# LumiBeePCB_v1A_2130spi_1.net
KiCad netlist of a schematic drawn in EAGLE
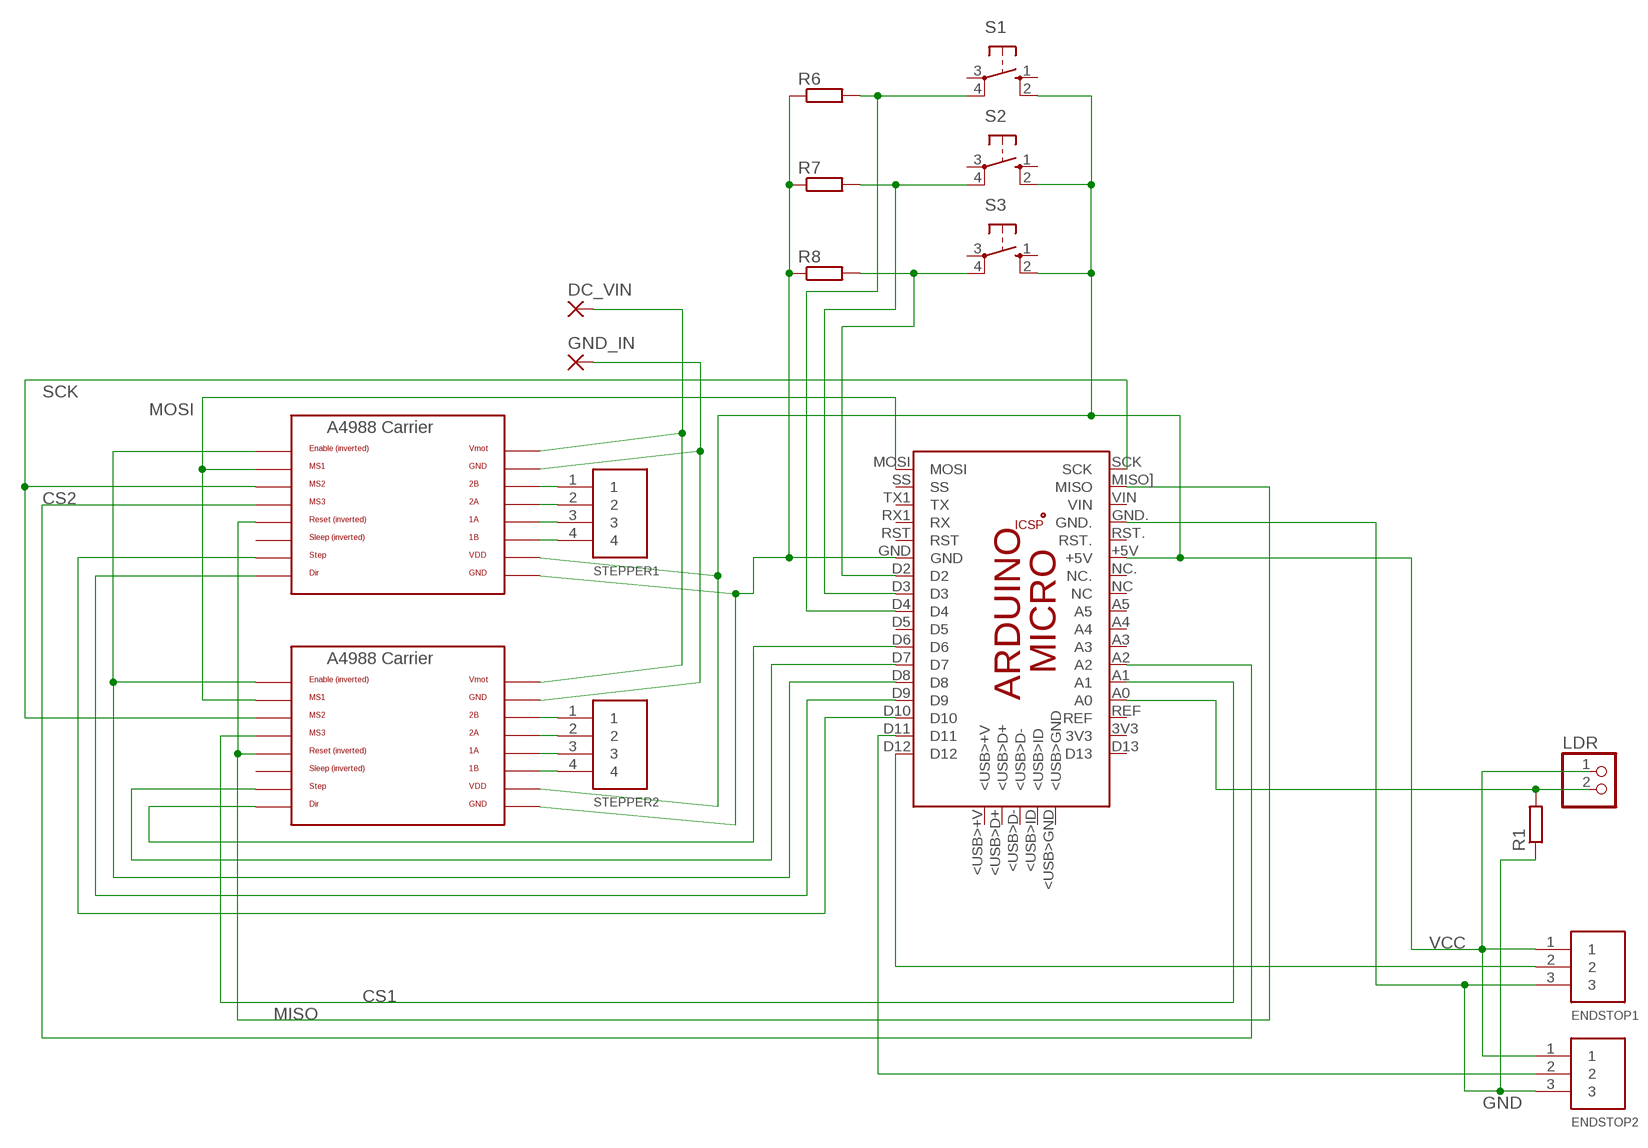
[diagram p0: schematic, sheet 1]

(export (version "E")
  (design (tool "Eeschema 10.0.6"))
  (components
    (comp (ref "DC_VIN")
      (value "2,54/0,8")
      (footprint "eagle-import:2,54_0,8")
      (libsource (lib "eagle-import") (part "2,54/0,8"))
    )
    (comp (ref "ENDSTOP1")
      (value "3PIN")
      (footprint "eagle-import:B3B-PH-K-S")
      (libsource (lib "eagle-import") (part "3PIN"))
    )
    (comp (ref "ENDSTOP2")
      (value "3PIN")
      (footprint "eagle-import:B3B-PH-K-S")
      (libsource (lib "eagle-import") (part "3PIN"))
    )
    (comp (ref "GND_IN")
      (value "2,54/0,8")
      (footprint "eagle-import:2,54_0,8")
      (libsource (lib "eagle-import") (part "2,54/0,8"))
    )
    (comp (ref "LDR")
      (value "PINHD-1X2")
      (footprint "eagle-import:1X02")
      (libsource (lib "eagle-import") (part "PINHD-1X2"))
    )
    (comp (ref "PCB1")
      (value "ARDUINO_MICRO")
      (footprint "eagle-import:ARDUINO_MICRO")
      (libsource (lib "eagle-import") (part "ARDUINO_MICRO"))
    )
    (comp (ref "R1")
      (value "R-EU_M1206")
      (footprint "eagle-import:M1206")
      (libsource (lib "eagle-import") (part "R-EU_M1206"))
    )
    (comp (ref "R6")
      (value "R-EU_M1206")
      (footprint "eagle-import:M1206")
      (libsource (lib "eagle-import") (part "R-EU_M1206"))
    )
    (comp (ref "R7")
      (value "R-EU_M1206")
      (footprint "eagle-import:M1206")
      (libsource (lib "eagle-import") (part "R-EU_M1206"))
    )
    (comp (ref "R8")
      (value "R-EU_M1206")
      (footprint "eagle-import:M1206")
      (libsource (lib "eagle-import") (part "R-EU_M1206"))
    )
    (comp (ref "S1")
      (value "10-XX")
      (footprint "eagle-import:B3F-10XX")
      (fields (field (name "MPN") "B3F-1000"))
      (libsource (lib "eagle-import") (part "10-XX"))
    )
    (comp (ref "S2")
      (value "10-XX")
      (footprint "eagle-import:B3F-10XX")
      (fields (field (name "MPN") "B3F-1000"))
      (libsource (lib "eagle-import") (part "10-XX"))
    )
    (comp (ref "S3")
      (value "10-XX")
      (footprint "eagle-import:B3F-10XX")
      (fields (field (name "MPN") "B3F-1000"))
      (libsource (lib "eagle-import") (part "10-XX"))
    )
    (comp (ref "STEPPER1")
      (value "4PIN")
      (footprint "eagle-import:B4B-PH-K-S")
      (libsource (lib "eagle-import") (part "4PIN"))
    )
    (comp (ref "STEPPER2")
      (value "4PIN")
      (footprint "eagle-import:B4B-PH-K-S")
      (libsource (lib "eagle-import") (part "4PIN"))
    )
    (comp (ref "U$1")
      (value "A4988BREAKOUT")
      (footprint "eagle-import:A4988BREAKOUT")
      (libsource (lib "eagle-import") (part "A4988BREAKOUT"))
    )
    (comp (ref "U$2")
      (value "A4988BREAKOUT")
      (footprint "eagle-import:A4988BREAKOUT")
      (libsource (lib "eagle-import") (part "A4988BREAKOUT"))
    )
  )
  (nets
    (net (code "1") (name "/CS1") (class "Default")
      (node (ref "PCB1") (pin "A1") (pinfunction "A1_A1") (pintype "bidirectional"))
      (node (ref "U$2") (pin "MS3") (pinfunction "MS3_MS3") (pintype "input"))
    )
    (net (code "2") (name "/CS2") (class "Default")
      (node (ref "PCB1") (pin "A2") (pinfunction "A2_A2") (pintype "bidirectional"))
      (node (ref "U$1") (pin "MS3") (pinfunction "MS3_MS3") (pintype "input"))
    )
    (net (code "3") (name "/GND") (class "Default")
      (node (ref "ENDSTOP1") (pin "3") (pinfunction "3_3") (pintype "bidirectional"))
      (node (ref "ENDSTOP2") (pin "3") (pinfunction "3_3") (pintype "bidirectional"))
      (node (ref "PCB1") (pin "GND.") (pinfunction "GND._GND.") (pintype "bidirectional"))
      (node (ref "R1") (pin "1") (pinfunction "1_1") (pintype "passive"))
    )
    (net (code "4") (name "/MISO") (class "Default")
      (node (ref "PCB1") (pin "MISO]") (pinfunction "MISO_MISO]") (pintype "bidirectional"))
      (node (ref "U$1") (pin "RST") (pinfunction "RST_RST") (pintype "input"))
      (node (ref "U$2") (pin "RST") (pinfunction "RST_RST") (pintype "input"))
    )
    (net (code "5") (name "/MOSI") (class "Default")
      (node (ref "PCB1") (pin "MOSI") (pinfunction "MOSI_MOSI") (pintype "bidirectional"))
      (node (ref "U$1") (pin "MS1") (pinfunction "MS1_MS1") (pintype "input"))
      (node (ref "U$2") (pin "MS1") (pinfunction "MS1_MS1") (pintype "input"))
    )
    (net (code "6") (name "/SCK") (class "Default")
      (node (ref "PCB1") (pin "SCK") (pinfunction "SCK_SCK") (pintype "bidirectional"))
      (node (ref "U$1") (pin "MS2") (pinfunction "MS2_MS2") (pintype "input"))
      (node (ref "U$2") (pin "MS2") (pinfunction "MS2_MS2") (pintype "input"))
    )
    (net (code "7") (name "/VCC") (class "Default")
      (node (ref "ENDSTOP1") (pin "1") (pinfunction "1_1") (pintype "bidirectional"))
      (node (ref "ENDSTOP2") (pin "1") (pinfunction "1_1") (pintype "bidirectional"))
      (node (ref "LDR") (pin "1") (pinfunction "1_1") (pintype "passive"))
      (node (ref "PCB1") (pin "+5V") (pinfunction "+5V_+5V") (pintype "bidirectional"))
      (node (ref "S1") (pin "2") (pinfunction "S1_2") (pintype "passive"))
      (node (ref "S2") (pin "2") (pinfunction "S1_2") (pintype "passive"))
      (node (ref "S3") (pin "2") (pinfunction "S1_2") (pintype "passive"))
      (node (ref "U$1") (pin "VDD") (pinfunction "VDD_VDD") (pintype "power_in"))
      (node (ref "U$2") (pin "VDD") (pinfunction "VDD_VDD") (pintype "power_in"))
    )
    (net (code "8") (name "Net-(DC_VIN-P)") (class "Default")
      (node (ref "DC_VIN") (pin "1") (pinfunction "P_1") (pintype "passive"))
      (node (ref "U$1") (pin "VMOT") (pinfunction "VMOT_VMOT") (pintype "power_in"))
      (node (ref "U$2") (pin "VMOT") (pinfunction "VMOT_VMOT") (pintype "power_in"))
    )
    (net (code "9") (name "Net-(ENDSTOP1-Pad2)") (class "Default")
      (node (ref "ENDSTOP1") (pin "2") (pinfunction "2_2") (pintype "bidirectional"))
      (node (ref "PCB1") (pin "D12") (pinfunction "D12_D12") (pintype "bidirectional"))
    )
    (net (code "10") (name "Net-(ENDSTOP2-Pad2)") (class "Default")
      (node (ref "ENDSTOP2") (pin "2") (pinfunction "2_2") (pintype "bidirectional"))
      (node (ref "PCB1") (pin "D11") (pinfunction "D11_D11") (pintype "bidirectional"))
    )
    (net (code "11") (name "Net-(GND_IN-P)") (class "Default")
      (node (ref "GND_IN") (pin "1") (pinfunction "P_1") (pintype "passive"))
      (node (ref "U$1") (pin "GND") (pinfunction "GND_GND") (pintype "power_in"))
      (node (ref "U$2") (pin "GND") (pinfunction "GND_GND") (pintype "power_in"))
    )
    (net (code "12") (name "Net-(LDR-Pad2)") (class "Default")
      (node (ref "LDR") (pin "2") (pinfunction "2_2") (pintype "passive"))
      (node (ref "PCB1") (pin "A0") (pinfunction "A0_A0") (pintype "bidirectional"))
      (node (ref "R1") (pin "2") (pinfunction "2_2") (pintype "passive"))
    )
    (net (code "13") (name "Net-(PCB1-PadD6)") (class "Default")
      (node (ref "PCB1") (pin "D6") (pinfunction "D6_D6") (pintype "bidirectional"))
      (node (ref "U$2") (pin "DIR") (pinfunction "DIR_DIR") (pintype "input"))
    )
    (net (code "14") (name "Net-(PCB1-PadD7)") (class "Default")
      (node (ref "PCB1") (pin "D7") (pinfunction "D7_D7") (pintype "bidirectional"))
      (node (ref "U$2") (pin "STEP") (pinfunction "STEP_STEP") (pintype "input"))
    )
    (net (code "15") (name "Net-(PCB1-PadD8)") (class "Default")
      (node (ref "PCB1") (pin "D8") (pinfunction "D8_D8") (pintype "bidirectional"))
      (node (ref "U$1") (pin "EN") (pinfunction "EN_EN") (pintype "input"))
      (node (ref "U$2") (pin "EN") (pinfunction "EN_EN") (pintype "input"))
    )
    (net (code "16") (name "Net-(PCB1-PadD9)") (class "Default")
      (node (ref "PCB1") (pin "D9") (pinfunction "D9_D9") (pintype "bidirectional"))
      (node (ref "U$1") (pin "DIR") (pinfunction "DIR_DIR") (pintype "input"))
    )
    (net (code "17") (name "Net-(PCB1-PadD10)") (class "Default")
      (node (ref "PCB1") (pin "D10") (pinfunction "D10_D10") (pintype "bidirectional"))
      (node (ref "U$1") (pin "STEP") (pinfunction "STEP_STEP") (pintype "input"))
    )
    (net (code "18") (name "Net-(PCB1-PadGND)") (class "Default")
      (node (ref "PCB1") (pin "GND") (pinfunction "GND_GND") (pintype "bidirectional"))
      (node (ref "R6") (pin "1") (pinfunction "1_1") (pintype "passive"))
      (node (ref "R7") (pin "1") (pinfunction "1_1") (pintype "passive"))
      (node (ref "R8") (pin "1") (pinfunction "1_1") (pintype "passive"))
      (node (ref "U$1") (pin "GND@0") (pinfunction "GND_GND@0") (pintype "power_in"))
      (node (ref "U$2") (pin "GND@0") (pinfunction "GND_GND@0") (pintype "power_in"))
    )
    (net (code "19") (name "Net-(S1-P1)") (class "Default")
      (node (ref "PCB1") (pin "D4") (pinfunction "D4_D4") (pintype "bidirectional"))
      (node (ref "R6") (pin "2") (pinfunction "2_2") (pintype "passive"))
      (node (ref "S1") (pin "4") (pinfunction "P1_4") (pintype "passive"))
    )
    (net (code "20") (name "Net-(S2-P1)") (class "Default")
      (node (ref "PCB1") (pin "D3") (pinfunction "D3_D3") (pintype "bidirectional"))
      (node (ref "R7") (pin "2") (pinfunction "2_2") (pintype "passive"))
      (node (ref "S2") (pin "4") (pinfunction "P1_4") (pintype "passive"))
    )
    (net (code "21") (name "Net-(S3-P1)") (class "Default")
      (node (ref "PCB1") (pin "D2") (pinfunction "D2_D2") (pintype "bidirectional"))
      (node (ref "R8") (pin "2") (pinfunction "2_2") (pintype "passive"))
      (node (ref "S3") (pin "4") (pinfunction "P1_4") (pintype "passive"))
    )
    (net (code "22") (name "Net-(STEPPER1-Pad1)") (class "Default")
      (node (ref "STEPPER1") (pin "1") (pinfunction "1_1") (pintype "bidirectional"))
      (node (ref "U$1") (pin "2B") (pinfunction "2B_2B") (pintype "output"))
    )
    (net (code "23") (name "Net-(STEPPER1-Pad2)") (class "Default")
      (node (ref "STEPPER1") (pin "2") (pinfunction "2_2") (pintype "bidirectional"))
      (node (ref "U$1") (pin "2A") (pinfunction "2A_2A") (pintype "output"))
    )
    (net (code "24") (name "Net-(STEPPER1-Pad3)") (class "Default")
      (node (ref "STEPPER1") (pin "3") (pinfunction "3_3") (pintype "bidirectional"))
      (node (ref "U$1") (pin "1A") (pinfunction "1A_1A") (pintype "output"))
    )
    (net (code "25") (name "Net-(STEPPER1-Pad4)") (class "Default")
      (node (ref "STEPPER1") (pin "4") (pinfunction "4_4") (pintype "bidirectional"))
      (node (ref "U$1") (pin "1B") (pinfunction "1B_1B") (pintype "output"))
    )
    (net (code "26") (name "Net-(STEPPER2-Pad1)") (class "Default")
      (node (ref "STEPPER2") (pin "1") (pinfunction "1_1") (pintype "bidirectional"))
      (node (ref "U$2") (pin "2B") (pinfunction "2B_2B") (pintype "output"))
    )
    (net (code "27") (name "Net-(STEPPER2-Pad2)") (class "Default")
      (node (ref "STEPPER2") (pin "2") (pinfunction "2_2") (pintype "bidirectional"))
      (node (ref "U$2") (pin "2A") (pinfunction "2A_2A") (pintype "output"))
    )
    (net (code "28") (name "Net-(STEPPER2-Pad3)") (class "Default")
      (node (ref "STEPPER2") (pin "3") (pinfunction "3_3") (pintype "bidirectional"))
      (node (ref "U$2") (pin "1A") (pinfunction "1A_1A") (pintype "output"))
    )
    (net (code "29") (name "Net-(STEPPER2-Pad4)") (class "Default")
      (node (ref "STEPPER2") (pin "4") (pinfunction "4_4") (pintype "bidirectional"))
      (node (ref "U$2") (pin "1B") (pinfunction "1B_1B") (pintype "output"))
    )
    (net (code "30") (name "unconnected-(PCB1-Pad3V3)") (class "Default")
      (node (ref "PCB1") (pin "3V3") (pinfunction "3V3_3V3") (pintype "bidirectional"))
    )
    (net (code "31") (name "unconnected-(PCB1-Pad5V)") (class "Default")
      (node (ref "PCB1") (pin "5V") (pinfunction "5V_5V") (pintype "bidirectional"))
    )
    (net (code "32") (name "unconnected-(PCB1-Pad<USB>+V)") (class "Default")
      (node (ref "PCB1") (pin "<USB>+V") (pinfunction "<USB>+V_<USB>+V") (pintype "bidirectional"))
    )
    (net (code "33") (name "unconnected-(PCB1-Pad<USB>D+)") (class "Default")
      (node (ref "PCB1") (pin "<USB>D+") (pinfunction "<USB>D+_<USB>D+") (pintype "bidirectional"))
    )
    (net (code "34") (name "unconnected-(PCB1-Pad<USB>D-)") (class "Default")
      (node (ref "PCB1") (pin "<USB>D-") (pinfunction "<USB>D-_<USB>D-") (pintype "bidirectional"))
    )
    (net (code "35") (name "unconnected-(PCB1-Pad<USB>GND)") (class "Default")
      (node (ref "PCB1") (pin "<USB>GND") (pinfunction "<USB>GND_<USB>GND") (pintype "bidirectional"))
    )
    (net (code "36") (name "unconnected-(PCB1-Pad<USB>ID)") (class "Default")
      (node (ref "PCB1") (pin "<USB>ID") (pinfunction "<USB>ID_<USB>ID") (pintype "bidirectional"))
    )
    (net (code "37") (name "unconnected-(PCB1-PadA3)") (class "Default")
      (node (ref "PCB1") (pin "A3") (pinfunction "A3_A3") (pintype "bidirectional"))
    )
    (net (code "38") (name "unconnected-(PCB1-PadA4)") (class "Default")
      (node (ref "PCB1") (pin "A4") (pinfunction "A4_A4") (pintype "bidirectional"))
    )
    (net (code "39") (name "unconnected-(PCB1-PadA5)") (class "Default")
      (node (ref "PCB1") (pin "A5") (pinfunction "A5_A5") (pintype "bidirectional"))
    )
    (net (code "40") (name "unconnected-(PCB1-PadD5)") (class "Default")
      (node (ref "PCB1") (pin "D5") (pinfunction "D5_D5") (pintype "bidirectional"))
    )
    (net (code "41") (name "unconnected-(PCB1-PadD13)") (class "Default")
      (node (ref "PCB1") (pin "D13") (pinfunction "D13_D13") (pintype "bidirectional"))
    )
    (net (code "42") (name "unconnected-(PCB1-PadGND_)") (class "Default")
      (node (ref "PCB1") (pin "GND_") (pinfunction "GND__GND_") (pintype "bidirectional"))
    )
    (net (code "43") (name "unconnected-(PCB1-PadMISO.)") (class "Default")
      (node (ref "PCB1") (pin "MISO.") (pinfunction "MISO._MISO.") (pintype "bidirectional"))
    )
    (net (code "44") (name "unconnected-(PCB1-PadMOSI.)") (class "Default")
      (node (ref "PCB1") (pin "MOSI.") (pinfunction "MOSI._MOSI.") (pintype "bidirectional"))
    )
    (net (code "45") (name "unconnected-(PCB1-PadNC)") (class "Default")
      (node (ref "PCB1") (pin "NC") (pinfunction "NC_NC") (pintype "bidirectional"))
    )
    (net (code "46") (name "unconnected-(PCB1-PadNC.)") (class "Default")
      (node (ref "PCB1") (pin "NC.") (pinfunction "NC._NC.") (pintype "bidirectional"))
    )
    (net (code "47") (name "unconnected-(PCB1-PadREF)") (class "Default")
      (node (ref "PCB1") (pin "REF") (pinfunction "REF_REF") (pintype "bidirectional"))
    )
    (net (code "48") (name "unconnected-(PCB1-PadRESET..)") (class "Default")
      (node (ref "PCB1") (pin "RESET..") (pinfunction "RESET.._RESET..") (pintype "bidirectional"))
    )
    (net (code "49") (name "unconnected-(PCB1-PadRST)") (class "Default")
      (node (ref "PCB1") (pin "RST") (pinfunction "RST_RST") (pintype "bidirectional"))
    )
    (net (code "50") (name "unconnected-(PCB1-PadRST.)") (class "Default")
      (node (ref "PCB1") (pin "RST.") (pinfunction "RST._RST.") (pintype "bidirectional"))
    )
    (net (code "51") (name "unconnected-(PCB1-PadSCK.)") (class "Default")
      (node (ref "PCB1") (pin "SCK.") (pinfunction "SCK._SCK.") (pintype "bidirectional"))
    )
    (net (code "52") (name "unconnected-(PCB1-PadSS)") (class "Default")
      (node (ref "PCB1") (pin "SS") (pinfunction "SS_SS") (pintype "bidirectional"))
    )
    (net (code "53") (name "unconnected-(PCB1-PadVIN)") (class "Default")
      (node (ref "PCB1") (pin "VIN") (pinfunction "VIN_VIN") (pintype "bidirectional"))
    )
    (net (code "54") (name "unconnected-(PCB1-RX-PadRX1)") (class "Default")
      (node (ref "PCB1") (pin "RX1") (pinfunction "RX_RX1") (pintype "bidirectional"))
    )
    (net (code "55") (name "unconnected-(PCB1-TX-PadTX1)") (class "Default")
      (node (ref "PCB1") (pin "TX1") (pinfunction "TX_TX1") (pintype "bidirectional"))
    )
    (net (code "56") (name "unconnected-(S1-P-Pad3)") (class "Default")
      (node (ref "S1") (pin "3") (pinfunction "P_3") (pintype "passive"))
    )
    (net (code "57") (name "unconnected-(S1-S-Pad1)") (class "Default")
      (node (ref "S1") (pin "1") (pinfunction "S_1") (pintype "passive"))
    )
    (net (code "58") (name "unconnected-(S2-P-Pad3)") (class "Default")
      (node (ref "S2") (pin "3") (pinfunction "P_3") (pintype "passive"))
    )
    (net (code "59") (name "unconnected-(S2-S-Pad1)") (class "Default")
      (node (ref "S2") (pin "1") (pinfunction "S_1") (pintype "passive"))
    )
    (net (code "60") (name "unconnected-(S3-P-Pad3)") (class "Default")
      (node (ref "S3") (pin "3") (pinfunction "P_3") (pintype "passive"))
    )
    (net (code "61") (name "unconnected-(S3-S-Pad1)") (class "Default")
      (node (ref "S3") (pin "1") (pinfunction "S_1") (pintype "passive"))
    )
    (net (code "62") (name "unconnected-(U$1-SLEEP-PadSLP)") (class "Default")
      (node (ref "U$1") (pin "SLP") (pinfunction "SLEEP_SLP") (pintype "input"))
    )
    (net (code "63") (name "unconnected-(U$2-SLEEP-PadSLP)") (class "Default")
      (node (ref "U$2") (pin "SLP") (pinfunction "SLEEP_SLP") (pintype "input"))
    )
  )
)
